# design.net
KiCad netlist of a schematic drawn in EasyEDA Pro
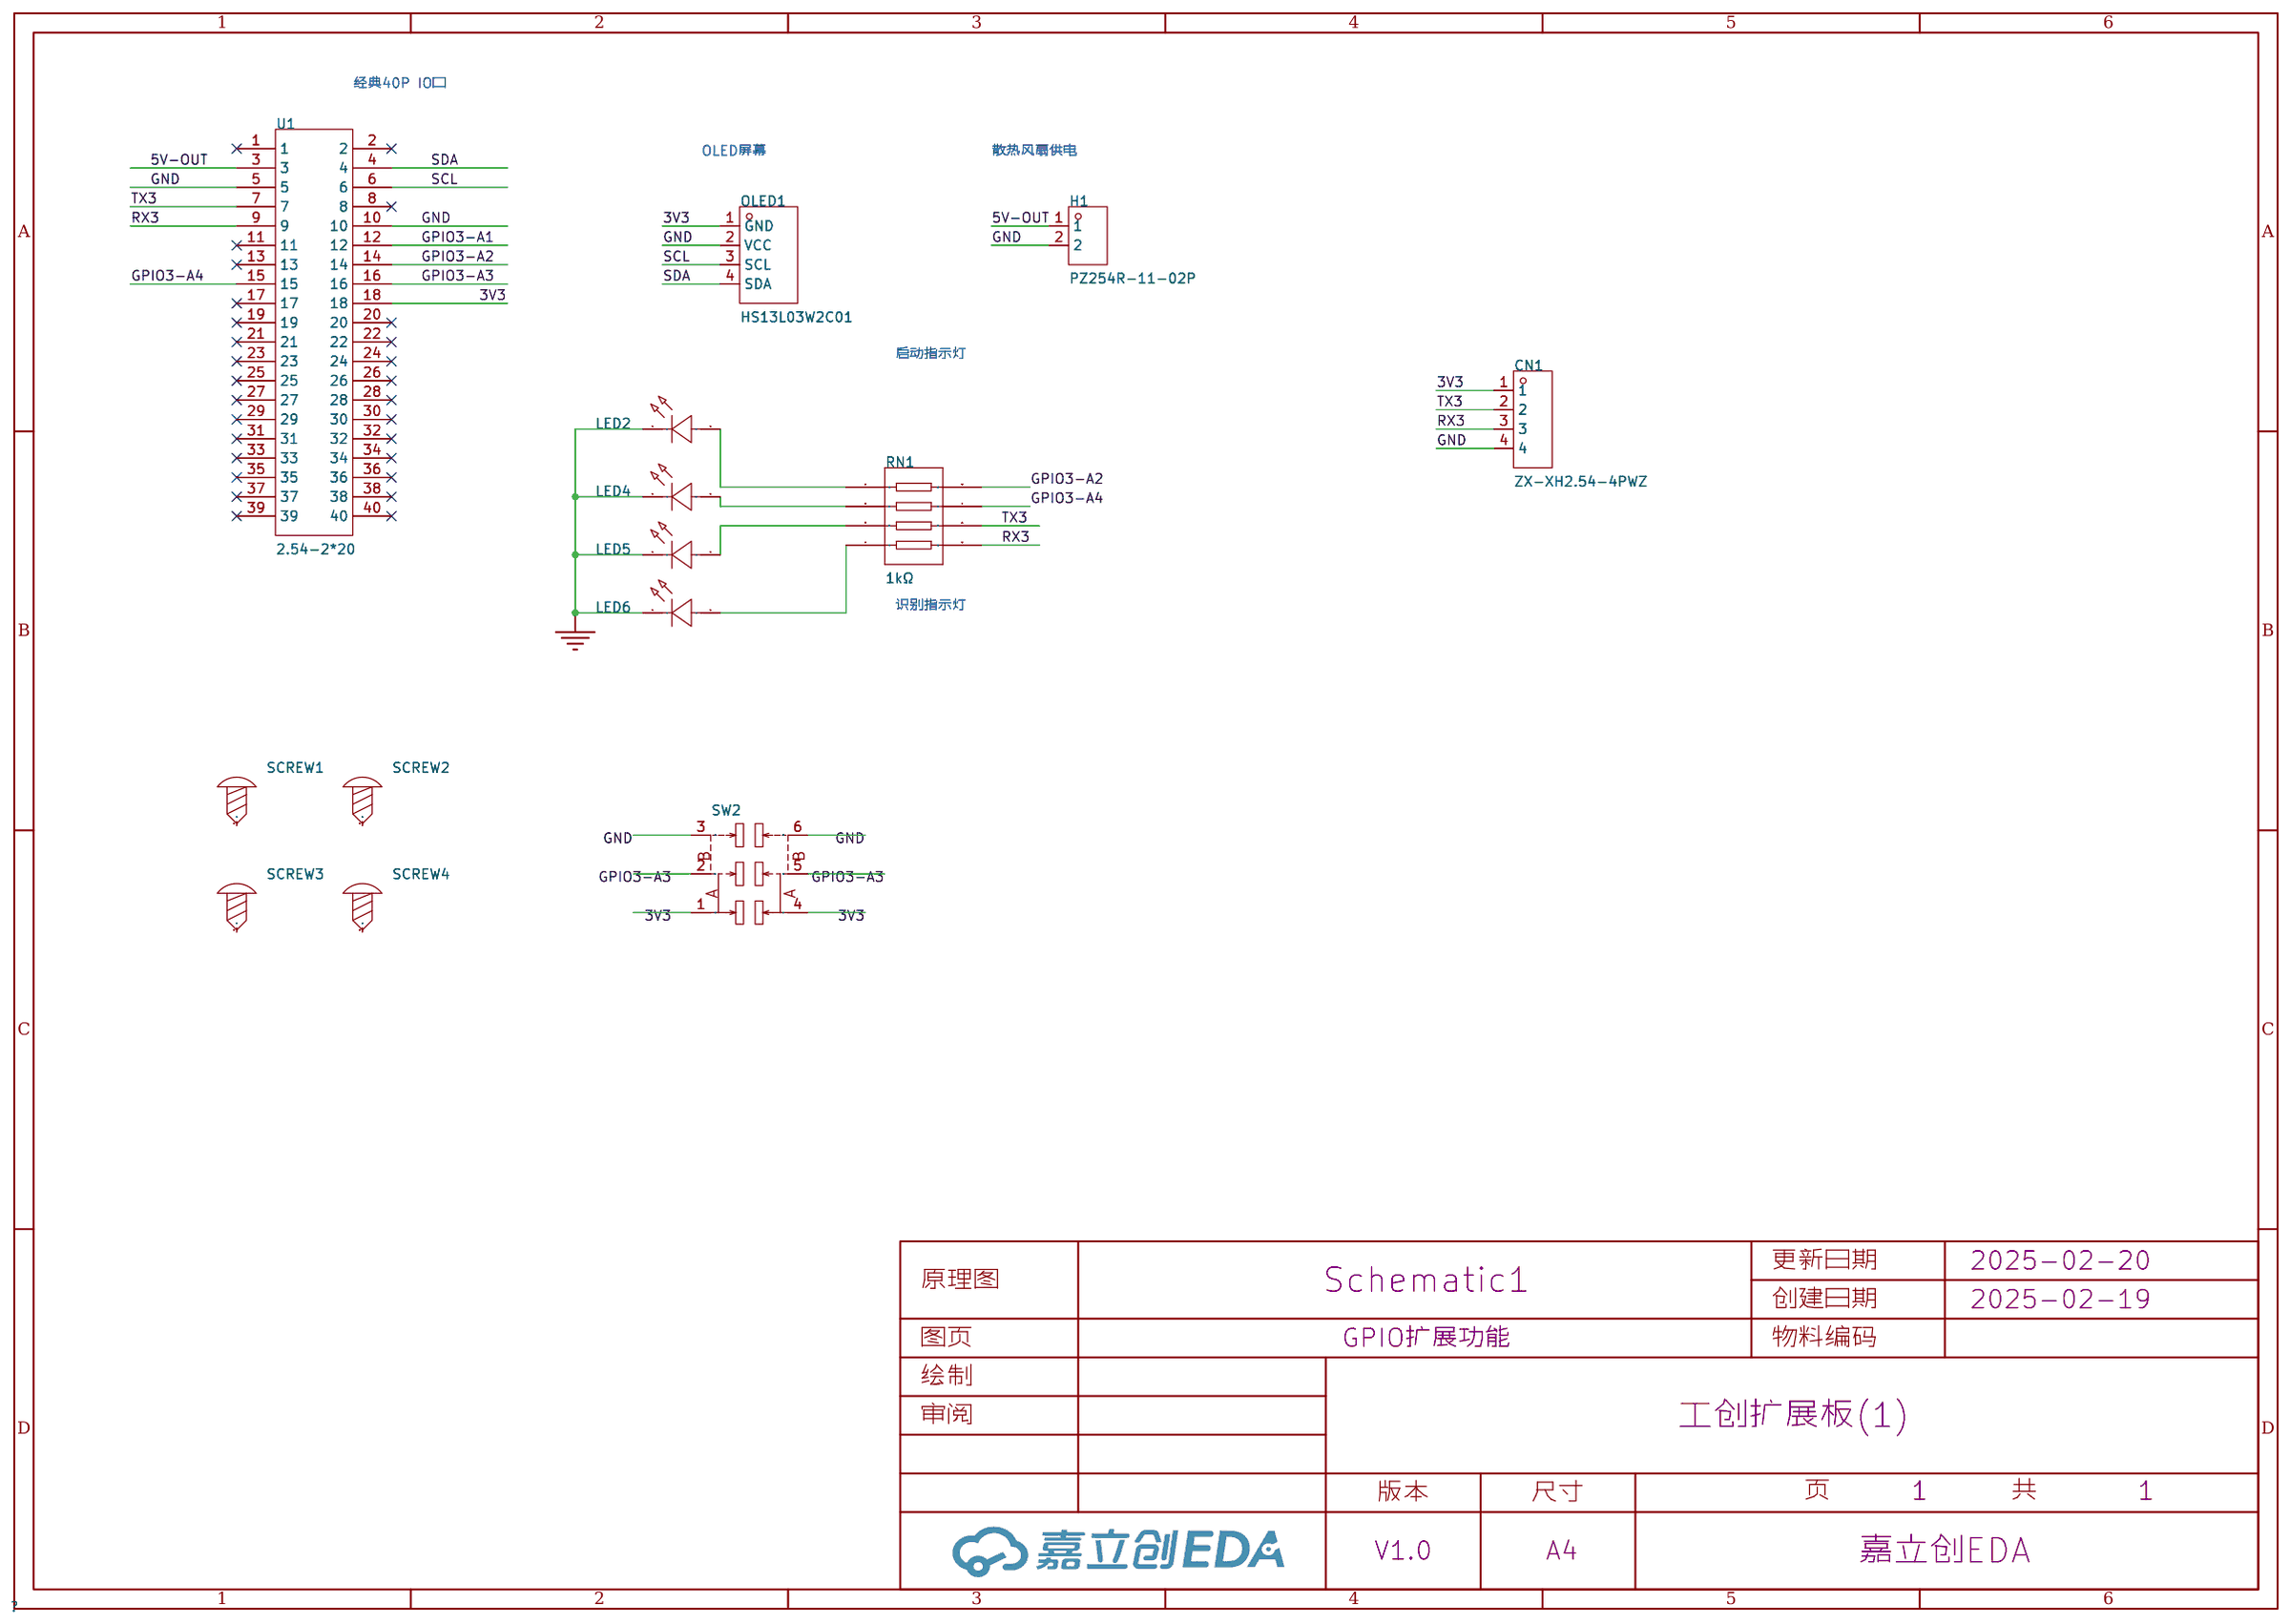
[diagram p0: schematic sheet]

(export (version "E")
  (design (tool "Eeschema 10.0.6"))
  (components
    (comp (ref "CN1")
      (value "ZX-XH2.54-4PWZ")
      (footprint "easyedapro:CONN-TH_4P-P2.50_ZX-XH2.54-4PWZ")
      (fields (field (name "Manufacturer") "Megastar(兆星)"))
      (libsource (lib "easyedapro") (part "ZX-XH2.54-4PWZ"))
    )
    (comp (ref "H1")
      (value "PZ254R-11-02P")
      (footprint "easyedapro:HDR-TH_2P-P2.54-H-M-W10.4")
      (fields (field (name "Manufacturer") "XFCN(兴飞)"))
      (libsource (lib "easyedapro") (part "PZ254R-11-02P"))
    )
    (comp (ref "LED2")
      (value "MHT192DUGCT")
      (footprint "easyedapro:LED0603-RD")
      (fields (field (name "Manufacturer") "MEIHUA(美华)"))
      (libsource (lib "easyedapro") (part "MHT192DUGCT"))
    )
    (comp (ref "LED4")
      (value "MHT192DUGCT")
      (footprint "easyedapro:LED0603-RD")
      (fields (field (name "Manufacturer") "MEIHUA(美华)"))
      (libsource (lib "easyedapro") (part "MHT192DUGCT"))
    )
    (comp (ref "LED5")
      (value "MHT192DUGCT")
      (footprint "easyedapro:LED0603-RD")
      (fields (field (name "Manufacturer") "MEIHUA(美华)"))
      (libsource (lib "easyedapro") (part "MHT192DUGCT"))
    )
    (comp (ref "LED6")
      (value "MHT192DUGCT")
      (footprint "easyedapro:LED0603-RD")
      (fields (field (name "Manufacturer") "MEIHUA(美华)"))
      (libsource (lib "easyedapro") (part "MHT192DUGCT"))
    )
    (comp (ref "OLED1")
      (value "HS13L03W2C01")
      (footprint "easyedapro:OLED-TH_L35.4-W33.5_HS13L03W2C01")
      (description "主控芯片:SH1106;接口类型:I2C;尺寸(inch):1.3;")
      (fields (field (name "Manufacturer") "HS(汉昇)"))
      (libsource (lib "easyedapro") (part "HS13L03W2C01"))
    )
    (comp (ref "RN1")
      (value "1kΩ")
      (footprint "easyedapro:RES-ARRAY-SMD_0603-8P-L3.2-W1.6-BL")
      (description "电阻器数:4;阻值:1kΩ;精度:±5%;单个元件功率:62.5mW;温度系数:±200ppm/°C;")
      (fields
        (field (name "Manufacturer Part") "4D03WGJ0102T5E")
        (field (name "Manufacturer") "UNI-ROYAL(厚声)")
      )
      (libsource (lib "easyedapro") (part "4D03WGJ0102T5E"))
    )
    (comp (ref "SCREW1")
      (value "~")
      (footprint "easyedapro:M3螺丝")
      (libsource (lib "easyedapro") (part "螺丝孔"))
    )
    (comp (ref "SCREW2")
      (value "~")
      (footprint "easyedapro:M3螺丝")
      (libsource (lib "easyedapro") (part "螺丝孔"))
    )
    (comp (ref "SCREW3")
      (value "~")
      (footprint "easyedapro:M3螺丝")
      (libsource (lib "easyedapro") (part "螺丝孔"))
    )
    (comp (ref "SCREW4")
      (value "~")
      (footprint "easyedapro:M3螺丝")
      (libsource (lib "easyedapro") (part "螺丝孔"))
    )
    (comp (ref "SW2")
      (value "MST22D18G2 125")
      (footprint "easyedapro:SW-SMD_MST22D18G2")
      (description "电路结构:双刀双掷;安装方式:立贴;开关颜色:黑色;额定电流(DC):100mA;额定电压(DC):12V;机械寿命:1万次;")
      (fields (field (name "Manufacturer") "SHOU HAN(首韩)"))
      (libsource (lib "easyedapro") (part "MST22D18G2 125"))
    )
    (comp (ref "U1")
      (value "2.54-2*20")
      (footprint "easyedapro:HDR-TH_40P-P2.54-V-F-R2-C20-S2.54")
      (fields (field (name "Manufacturer") "ZHOURI(洲日)"))
      (libsource (lib "easyedapro") (part "2.54-2*20"))
    )
  )
  (nets
    (net (code "1") (name "/3V3") (class "Default")
      (node (ref "CN1") (pin "1") (pinfunction "1_1") (pintype "unspecified"))
      (node (ref "OLED1") (pin "1") (pinfunction "GND_1") (pintype "unspecified"))
      (node (ref "SW2") (pin "1") (pinfunction "1_1") (pintype "unspecified"))
      (node (ref "SW2") (pin "4") (pinfunction "4_4") (pintype "unspecified"))
      (node (ref "U1") (pin "18") (pinfunction "18_18") (pintype "unspecified"))
    )
    (net (code "2") (name "/5V-OUT") (class "Default")
      (node (ref "H1") (pin "1") (pinfunction "1_1") (pintype "unspecified"))
      (node (ref "U1") (pin "3") (pinfunction "3_3") (pintype "unspecified"))
    )
    (net (code "3") (name "/GPIO3-A1") (class "Default")
      (node (ref "U1") (pin "12") (pinfunction "12_12") (pintype "unspecified"))
    )
    (net (code "4") (name "/GPIO3-A2") (class "Default")
      (node (ref "RN1") (pin "8") (pinfunction "8_8") (pintype "input"))
      (node (ref "U1") (pin "14") (pinfunction "14_14") (pintype "unspecified"))
    )
    (net (code "5") (name "/GPIO3-A3") (class "Default")
      (node (ref "SW2") (pin "2") (pinfunction "2_2") (pintype "unspecified"))
      (node (ref "SW2") (pin "5") (pinfunction "5_5") (pintype "unspecified"))
      (node (ref "U1") (pin "16") (pinfunction "16_16") (pintype "unspecified"))
    )
    (net (code "6") (name "/GPIO3-A4") (class "Default")
      (node (ref "RN1") (pin "7") (pinfunction "7_7") (pintype "input"))
      (node (ref "U1") (pin "15") (pinfunction "15_15") (pintype "unspecified"))
    )
    (net (code "7") (name "/RX3") (class "Default")
      (node (ref "CN1") (pin "3") (pinfunction "3_3") (pintype "unspecified"))
      (node (ref "RN1") (pin "5") (pinfunction "5_5") (pintype "input"))
      (node (ref "U1") (pin "9") (pinfunction "9_9") (pintype "unspecified"))
    )
    (net (code "8") (name "/SCL") (class "Default")
      (node (ref "OLED1") (pin "3") (pinfunction "SCL_3") (pintype "unspecified"))
      (node (ref "U1") (pin "6") (pinfunction "6_6") (pintype "unspecified"))
    )
    (net (code "9") (name "/SDA") (class "Default")
      (node (ref "OLED1") (pin "4") (pinfunction "SDA_4") (pintype "unspecified"))
      (node (ref "U1") (pin "4") (pinfunction "4_4") (pintype "unspecified"))
    )
    (net (code "10") (name "/TX3") (class "Default")
      (node (ref "CN1") (pin "2") (pinfunction "2_2") (pintype "unspecified"))
      (node (ref "RN1") (pin "6") (pinfunction "6_6") (pintype "input"))
      (node (ref "U1") (pin "7") (pinfunction "7_7") (pintype "unspecified"))
    )
    (net (code "11") (name "GND") (class "Default")
      (node (ref "CN1") (pin "4") (pinfunction "4_4") (pintype "unspecified"))
      (node (ref "H1") (pin "2") (pinfunction "2_2") (pintype "unspecified"))
      (node (ref "LED2") (pin "1") (pinfunction "K_1") (pintype "unspecified"))
      (node (ref "LED4") (pin "1") (pinfunction "K_1") (pintype "unspecified"))
      (node (ref "LED5") (pin "1") (pinfunction "K_1") (pintype "unspecified"))
      (node (ref "LED6") (pin "1") (pinfunction "K_1") (pintype "unspecified"))
      (node (ref "OLED1") (pin "2") (pinfunction "VCC_2") (pintype "unspecified"))
      (node (ref "SW2") (pin "3") (pinfunction "3_3") (pintype "unspecified"))
      (node (ref "SW2") (pin "6") (pinfunction "6_6") (pintype "unspecified"))
      (node (ref "U1") (pin "10") (pinfunction "10_10") (pintype "unspecified"))
      (node (ref "U1") (pin "5") (pinfunction "5_5") (pintype "unspecified"))
    )
    (net (code "12") (name "Net-(LED2-A)") (class "Default")
      (node (ref "LED2") (pin "2") (pinfunction "A_2") (pintype "unspecified"))
      (node (ref "RN1") (pin "1") (pinfunction "1_1") (pintype "input"))
    )
    (net (code "13") (name "Net-(LED4-A)") (class "Default")
      (node (ref "LED4") (pin "2") (pinfunction "A_2") (pintype "unspecified"))
      (node (ref "RN1") (pin "2") (pinfunction "2_2") (pintype "input"))
    )
    (net (code "14") (name "Net-(LED5-A)") (class "Default")
      (node (ref "LED5") (pin "2") (pinfunction "A_2") (pintype "unspecified"))
      (node (ref "RN1") (pin "3") (pinfunction "3_3") (pintype "input"))
    )
    (net (code "15") (name "Net-(LED6-A)") (class "Default")
      (node (ref "LED6") (pin "2") (pinfunction "A_2") (pintype "unspecified"))
      (node (ref "RN1") (pin "4") (pinfunction "4_4") (pintype "input"))
    )
    (net (code "16") (name "unconnected-(SCREW1-Pad1)") (class "Default")
      (node (ref "SCREW1") (pin "1") (pinfunction "1_1") (pintype "input"))
    )
    (net (code "17") (name "unconnected-(SCREW2-Pad1)") (class "Default")
      (node (ref "SCREW2") (pin "1") (pinfunction "1_1") (pintype "input"))
    )
    (net (code "18") (name "unconnected-(SCREW3-Pad1)") (class "Default")
      (node (ref "SCREW3") (pin "1") (pinfunction "1_1") (pintype "input"))
    )
    (net (code "19") (name "unconnected-(SCREW4-Pad1)") (class "Default")
      (node (ref "SCREW4") (pin "1") (pinfunction "1_1") (pintype "input"))
    )
    (net (code "20") (name "unconnected-(U1-Pad1)") (class "Default")
      (node (ref "U1") (pin "1") (pinfunction "1_1") (pintype "unspecified+no_connect"))
    )
    (net (code "21") (name "unconnected-(U1-Pad2)") (class "Default")
      (node (ref "U1") (pin "2") (pinfunction "2_2") (pintype "unspecified+no_connect"))
    )
    (net (code "22") (name "unconnected-(U1-Pad8)") (class "Default")
      (node (ref "U1") (pin "8") (pinfunction "8_8") (pintype "unspecified+no_connect"))
    )
    (net (code "23") (name "unconnected-(U1-Pad11)") (class "Default")
      (node (ref "U1") (pin "11") (pinfunction "11_11") (pintype "unspecified+no_connect"))
    )
    (net (code "24") (name "unconnected-(U1-Pad13)") (class "Default")
      (node (ref "U1") (pin "13") (pinfunction "13_13") (pintype "unspecified+no_connect"))
    )
    (net (code "25") (name "unconnected-(U1-Pad17)") (class "Default")
      (node (ref "U1") (pin "17") (pinfunction "17_17") (pintype "unspecified+no_connect"))
    )
    (net (code "26") (name "unconnected-(U1-Pad19)") (class "Default")
      (node (ref "U1") (pin "19") (pinfunction "19_19") (pintype "unspecified+no_connect"))
    )
    (net (code "27") (name "unconnected-(U1-Pad20)") (class "Default")
      (node (ref "U1") (pin "20") (pinfunction "20_20") (pintype "unspecified+no_connect"))
    )
    (net (code "28") (name "unconnected-(U1-Pad21)") (class "Default")
      (node (ref "U1") (pin "21") (pinfunction "21_21") (pintype "unspecified+no_connect"))
    )
    (net (code "29") (name "unconnected-(U1-Pad22)") (class "Default")
      (node (ref "U1") (pin "22") (pinfunction "22_22") (pintype "unspecified+no_connect"))
    )
    (net (code "30") (name "unconnected-(U1-Pad23)") (class "Default")
      (node (ref "U1") (pin "23") (pinfunction "23_23") (pintype "unspecified+no_connect"))
    )
    (net (code "31") (name "unconnected-(U1-Pad24)") (class "Default")
      (node (ref "U1") (pin "24") (pinfunction "24_24") (pintype "unspecified+no_connect"))
    )
    (net (code "32") (name "unconnected-(U1-Pad25)") (class "Default")
      (node (ref "U1") (pin "25") (pinfunction "25_25") (pintype "unspecified+no_connect"))
    )
    (net (code "33") (name "unconnected-(U1-Pad26)") (class "Default")
      (node (ref "U1") (pin "26") (pinfunction "26_26") (pintype "unspecified+no_connect"))
    )
    (net (code "34") (name "unconnected-(U1-Pad27)") (class "Default")
      (node (ref "U1") (pin "27") (pinfunction "27_27") (pintype "unspecified+no_connect"))
    )
    (net (code "35") (name "unconnected-(U1-Pad28)") (class "Default")
      (node (ref "U1") (pin "28") (pinfunction "28_28") (pintype "unspecified+no_connect"))
    )
    (net (code "36") (name "unconnected-(U1-Pad29)") (class "Default")
      (node (ref "U1") (pin "29") (pinfunction "29_29") (pintype "unspecified+no_connect"))
    )
    (net (code "37") (name "unconnected-(U1-Pad30)") (class "Default")
      (node (ref "U1") (pin "30") (pinfunction "30_30") (pintype "unspecified+no_connect"))
    )
    (net (code "38") (name "unconnected-(U1-Pad31)") (class "Default")
      (node (ref "U1") (pin "31") (pinfunction "31_31") (pintype "unspecified+no_connect"))
    )
    (net (code "39") (name "unconnected-(U1-Pad32)") (class "Default")
      (node (ref "U1") (pin "32") (pinfunction "32_32") (pintype "unspecified+no_connect"))
    )
    (net (code "40") (name "unconnected-(U1-Pad33)") (class "Default")
      (node (ref "U1") (pin "33") (pinfunction "33_33") (pintype "unspecified+no_connect"))
    )
    (net (code "41") (name "unconnected-(U1-Pad34)") (class "Default")
      (node (ref "U1") (pin "34") (pinfunction "34_34") (pintype "unspecified+no_connect"))
    )
    (net (code "42") (name "unconnected-(U1-Pad35)") (class "Default")
      (node (ref "U1") (pin "35") (pinfunction "35_35") (pintype "unspecified+no_connect"))
    )
    (net (code "43") (name "unconnected-(U1-Pad36)") (class "Default")
      (node (ref "U1") (pin "36") (pinfunction "36_36") (pintype "unspecified+no_connect"))
    )
    (net (code "44") (name "unconnected-(U1-Pad37)") (class "Default")
      (node (ref "U1") (pin "37") (pinfunction "37_37") (pintype "unspecified+no_connect"))
    )
    (net (code "45") (name "unconnected-(U1-Pad38)") (class "Default")
      (node (ref "U1") (pin "38") (pinfunction "38_38") (pintype "unspecified+no_connect"))
    )
    (net (code "46") (name "unconnected-(U1-Pad39)") (class "Default")
      (node (ref "U1") (pin "39") (pinfunction "39_39") (pintype "unspecified+no_connect"))
    )
    (net (code "47") (name "unconnected-(U1-Pad40)") (class "Default")
      (node (ref "U1") (pin "40") (pinfunction "40_40") (pintype "unspecified+no_connect"))
    )
  )
)
